# Micro_Clock.net
KiCad netlist of a schematic drawn in Altium Designer
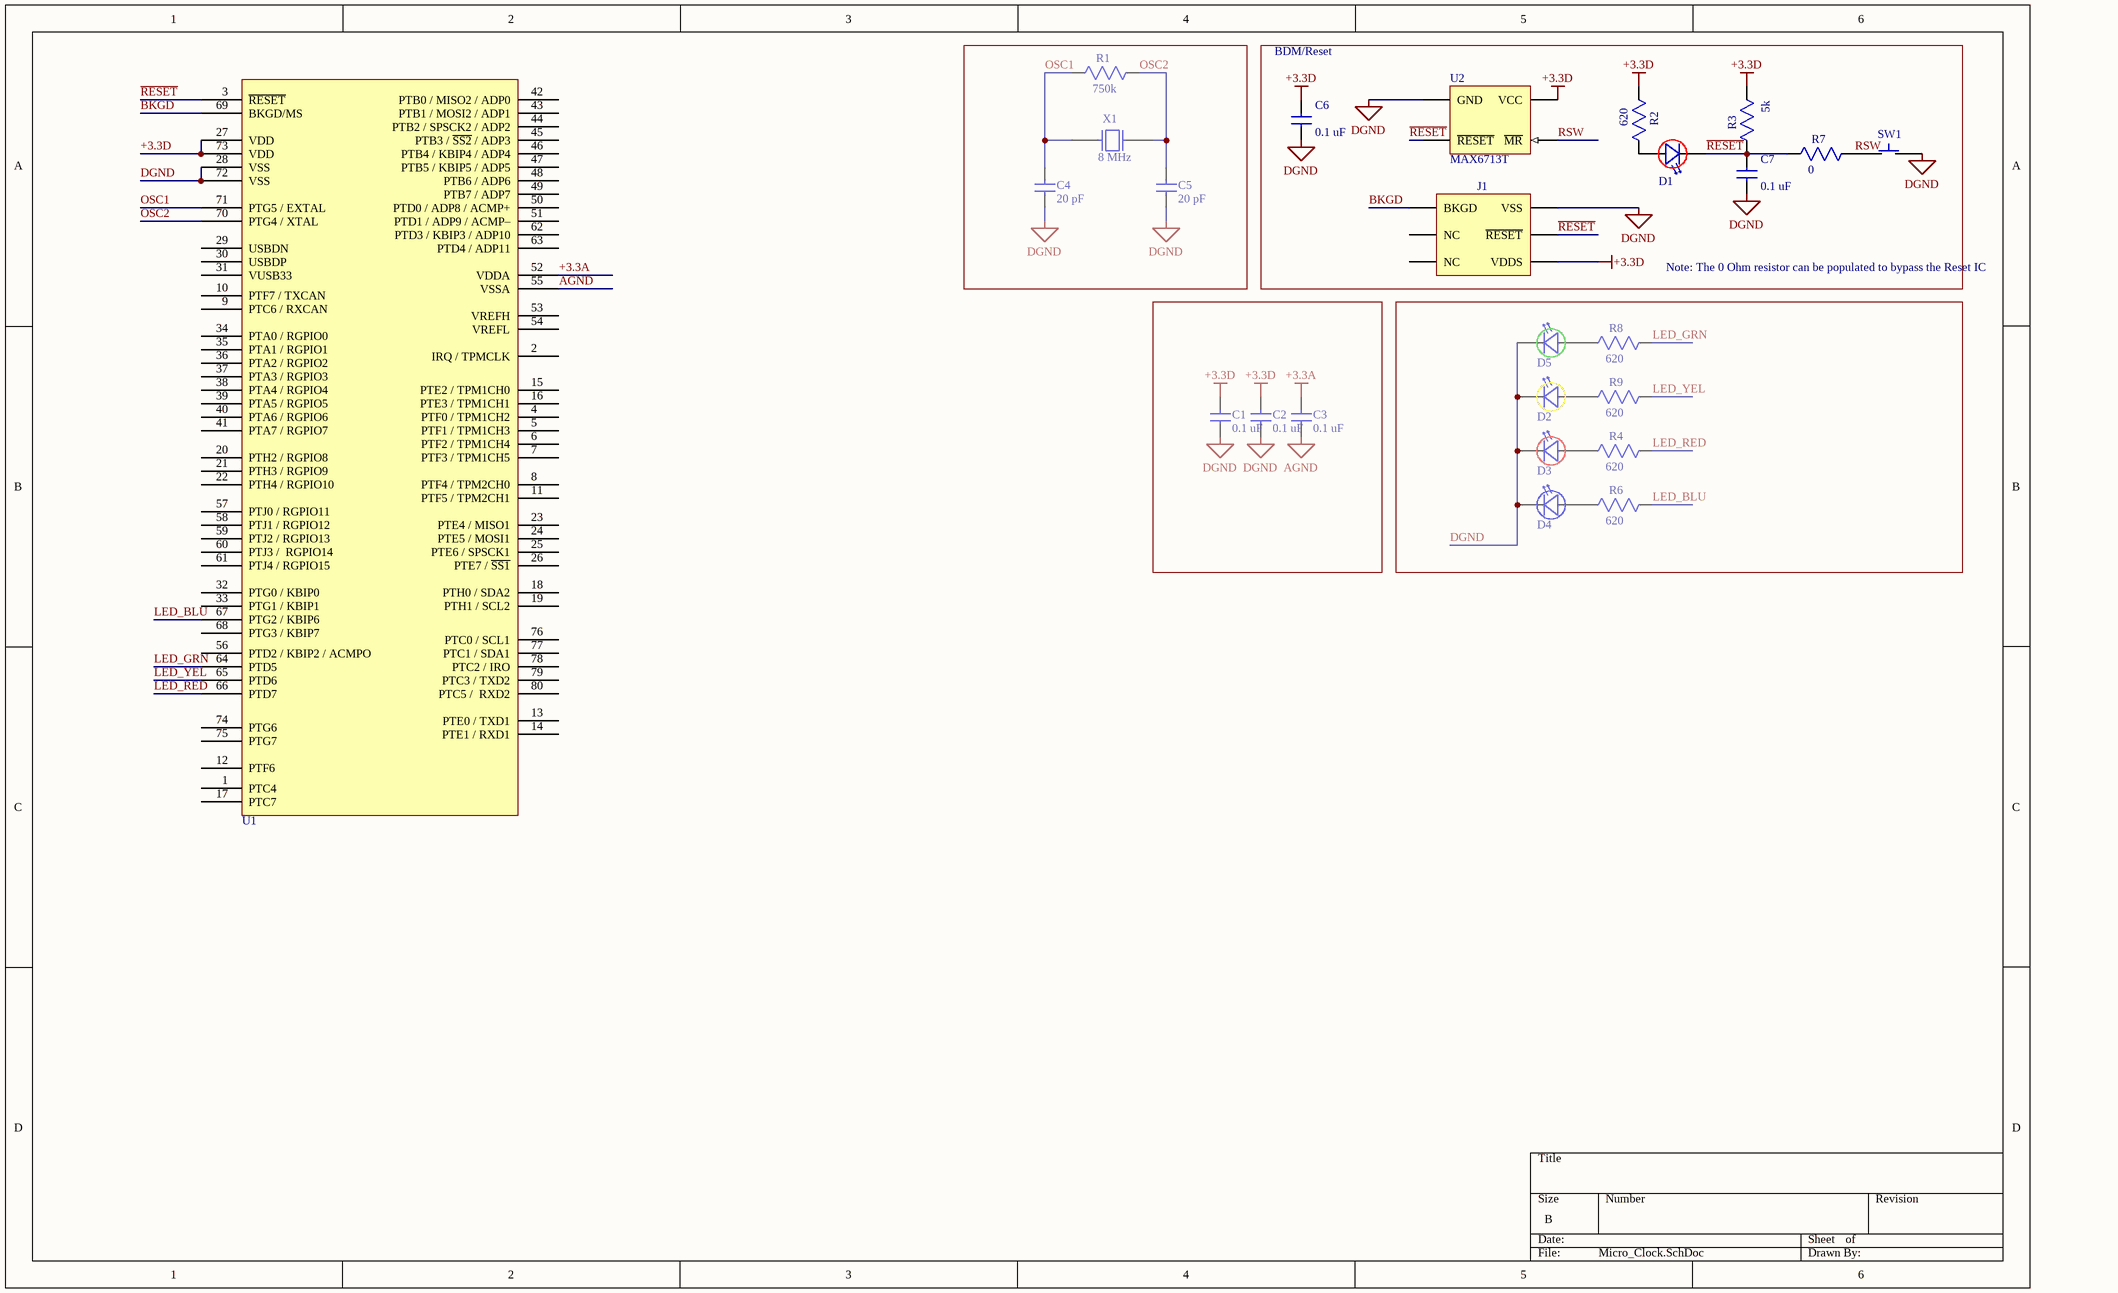
[diagram p0: Micro_Clock.SchDoc]

(export (version "E")
  (design (tool "Eeschema 10.0.6"))
  (components
    (comp (ref "C1")
      (value "0.1 uF")
      (footprint "0805")
      (description "CAP CERM 0.1uF")
      (fields
        (field (name "MANUFACTURER") "Yageo")
        (field (name "Comment") "CAP 0.1uF")
        (field (name "SVP CREATOR") "Brett Paulsen")
      )
      (libsource (lib "c3_SchLib") (part "C_0805_0.1uF_1"))
    )
    (comp (ref "C2")
      (value "0.1 uF")
      (footprint "0805")
      (description "CAP CERM 0.1uF")
      (fields
        (field (name "MANUFACTURER") "Yageo")
        (field (name "Comment") "CAP 0.1uF")
        (field (name "SVP CREATOR") "Brett Paulsen")
      )
      (libsource (lib "c3_SchLib") (part "C_0805_0.1uF_1"))
    )
    (comp (ref "C3")
      (value "0.1 uF")
      (footprint "0805")
      (description "CAP CERM 0.1uF")
      (fields
        (field (name "MANUFACTURER") "Yageo")
        (field (name "Comment") "CAP 0.1uF")
        (field (name "SVP CREATOR") "Brett Paulsen")
      )
      (libsource (lib "c3_SchLib") (part "C_0805_0.1uF_1"))
    )
    (comp (ref "C4")
      (value "20 pF")
      (footprint "0805")
      (description "CAP CERM 20PF 5% 100V NP0 0805")
      (fields
        (field (name "MANUFACTURER") "AVX")
        (field (name "Comment") "CAP 20PF")
        (field (name "SVP CREATOR") "Jonathan Nutzmann")
      )
      (libsource (lib "c3_SchLib") (part "C_0805_20PF_100V_5%"))
    )
    (comp (ref "C5")
      (value "20 pF")
      (footprint "0805")
      (description "CAP CERM 20PF 5% 100V NP0 0805")
      (fields
        (field (name "MANUFACTURER") "AVX")
        (field (name "Comment") "CAP 20PF")
        (field (name "SVP CREATOR") "Jonathan Nutzmann")
      )
      (libsource (lib "c3_SchLib") (part "C_0805_20PF_100V_5%"))
    )
    (comp (ref "C6")
      (value "0.1 uF")
      (footprint "0805")
      (description "CAP CERM 0.1uF")
      (fields
        (field (name "MANUFACTURER") "Yageo")
        (field (name "Comment") "CAP 0.1uF")
        (field (name "SVP CREATOR") "Brett Paulsen")
      )
      (libsource (lib "c3_SchLib") (part "C_0805_0.1uF_1"))
    )
    (comp (ref "C7")
      (value "0.1 uF")
      (footprint "0805")
      (description "CAP CERM 0.1uF")
      (fields
        (field (name "MANUFACTURER") "Yageo")
        (field (name "Comment") "CAP 0.1uF")
        (field (name "SVP CREATOR") "Brett Paulsen")
      )
      (libsource (lib "c3_SchLib") (part "C_0805_0.1uF_1"))
    )
    (comp (ref "D1")
      (value "D_LED_0805_RED")
      (footprint "0805P")
      (description "LED CHIPLED 645NM RED DIFF 0805")
      (fields (field (name "SVP CREATOR") "Jonathan Nutzmann"))
      (libsource (lib "c3_SchLib") (part "D_LED_0805_RED"))
    )
    (comp (ref "D2")
      (value "D_LED_0805_YELLOW")
      (footprint "0805P")
      (description "LED 595NM AMBER DIFF SMD 0805")
      (fields (field (name "SVP CREATOR") "Jonathan Nutzmann"))
      (libsource (lib "c3_SchLib") (part "D_LED_0805_YELLOW"))
    )
    (comp (ref "D3")
      (value "D_LED_0805_RED")
      (footprint "0805P")
      (description "LED CHIPLED 645NM RED DIFF 0805")
      (fields (field (name "SVP CREATOR") "Jonathan Nutzmann"))
      (libsource (lib "c3_SchLib") (part "D_LED_0805_RED"))
    )
    (comp (ref "D4")
      (value "D_LED_0805_BLUE")
      (footprint "0805P")
      (description "LED 2X1.2MM 470NM BL WTR CLR SMD")
      (fields (field (name "SVP CREATOR") "Jonathan Nutzmann"))
      (libsource (lib "c3_SchLib") (part "D_LED_0805_BLUE"))
    )
    (comp (ref "D5")
      (value "D_LED_0805_GREEN")
      (footprint "0805P")
      (description "LED CHIPLED 570NM GREEN 0805 SMD")
      (fields
        (field (name "MANUFACTURER") "Osram Opto Semiconductors Inc")
        (field (name "SVP CREATOR") "Nate Bolyard")
        (field (name "SVP REVIEWER 1") "Trevtron")
      )
      (libsource (lib "c3_SchLib") (part "D_LED_0805_GREEN"))
    )
    (comp (ref "J1")
      (value "BDM HHEADER")
      (footprint "BDM_HEADER")
      (description "BDM HEADER")
      (fields (field (name "SVP CREATOR") "Nate Bolyard"))
      (libsource (lib "c3_SchLib") (part "J_BDM_HEADER"))
    )
    (comp (ref "R1")
      (value "750k")
      (footprint "0805")
      (description "RES 750K OHM 1/8W 1% 0805 SMD")
      (fields
        (field (name "MANUFACTURER") "Rohm Semiconductor")
        (field (name "Comment") "R_0805_750k_1%")
        (field (name "SVP CREATOR") "Jonathan Nutzmann")
      )
      (libsource (lib "c3_SchLib") (part "R_0805_750k_1%"))
    )
    (comp (ref "R2")
      (value "620")
      (footprint "0805")
      (description "RES 620 OHM 1/8W 1% 0805 SMD")
      (fields (field (name "Comment") "R_0805_620_1%") (field (name "SVP CREATOR") "Jonathan Nutzmann"))
      (libsource (lib "c3_SchLib") (part "R_0805_620_1%"))
    )
    (comp (ref "R3")
      (value "5k")
      (footprint "0805")
      (description "RES 5K OHM 1/8W 1% 0805 SMD")
      (fields (field (name "Comment") "R_0805_5k") (field (name "SVP CREATOR") "Jonathan Nutzmann"))
      (libsource (lib "c3_SchLib") (part "R_0805_5K_1%"))
    )
    (comp (ref "R4")
      (value "620")
      (footprint "0805")
      (description "RES 620 OHM 1/8W 1% 0805 SMD")
      (fields (field (name "Comment") "R_0805_620_1%") (field (name "SVP CREATOR") "Jonathan Nutzmann"))
      (libsource (lib "c3_SchLib") (part "R_0805_620_1%"))
    )
    (comp (ref "R6")
      (value "620")
      (footprint "0805")
      (description "RES 620 OHM 1/8W 1% 0805 SMD")
      (fields (field (name "Comment") "R_0805_620_1%") (field (name "SVP CREATOR") "Jonathan Nutzmann"))
      (libsource (lib "c3_SchLib") (part "R_0805_620_1%"))
    )
    (comp (ref "R7")
      (value "0")
      (footprint "0805")
      (description "RES 0 OHM 0805 SMD")
      (fields (field (name "Comment") "R_0805_0") (field (name "SVP CREATOR") "Jonathan Nutzmann"))
      (libsource (lib "c3_SchLib") (part "R_0805_0"))
    )
    (comp (ref "R8")
      (value "620")
      (footprint "0805")
      (description "RES 620 OHM 1/8W 1% 0805 SMD")
      (fields (field (name "Comment") "R_0805_620_1%") (field (name "SVP CREATOR") "Jonathan Nutzmann"))
      (libsource (lib "c3_SchLib") (part "R_0805_620_1%"))
    )
    (comp (ref "R9")
      (value "620")
      (footprint "0805")
      (description "RES 620 OHM 1/8W 1% 0805 SMD")
      (fields (field (name "Comment") "R_0805_620_1%") (field (name "SVP CREATOR") "Jonathan Nutzmann"))
      (libsource (lib "c3_SchLib") (part "R_0805_620_1%"))
    )
    (comp (ref "SW1")
      (value "SW_TACT_SWITCH_6x6")
      (footprint "TACT_SWITCH_6x6")
      (description "SWITCH TACT 6MM BLACK 160GF")
      (fields (field (name "MANUFACTURER") "Tyco Electronics") (field (name "SVP CREATOR") "Nate Bolyard"))
      (libsource (lib "c3_SchLib") (part "SW_TACT_SWITCH_6x6"))
    )
    (comp (ref "U1")
      (value "C3 Microcontroller")
      (footprint "QFN_80_65P")
      (description "IC MCU 128/16K FLASH/SRAM 80LQFP")
      (fields (field (name "MANUFACTURER") "Microchip") (field (name "SVP CREATOR") "Jonathan Nutzmann"))
      (libsource (lib "c3_SchLib") (part "U_MCF51JM128VLK"))
    )
    (comp (ref "U2")
      (value "MAX6713T")
      (footprint "SC70")
      (description "MAX6713T Reset controller")
      (fields
        (field (name "MANUFACTURER") "Maxim")
        (field (name "Comment") "U_MAX6713T")
        (field (name "SVP CREATOR") "Nate Bolyard")
      )
      (libsource (lib "c3_SchLib") (part "U_MAX6713T"))
    )
    (comp (ref "X1")
      (value "8 MHz")
      (footprint "HC-49")
      (description "CRYSTAL 8.00 MHZ 20PF 49US")
      (fields
        (field (name "MANUFACTURER") "ECS")
        (field (name "Comment") "HC49")
        (field (name "SVP CREATOR") "Jonathan Nutzmann")
      )
      (libsource (lib "c3_SchLib") (part "X_HC49"))
    )
  )
  (nets
    (net (code "1") (name "+3.3A") (class "Default")
      (node (ref "C3") (pin "2") (pinfunction "2_2") (pintype "passive"))
      (node (ref "U1") (pin "52") (pinfunction "VDDA_52") (pintype "passive"))
    )
    (net (code "2") (name "+3.3D") (class "Default")
      (node (ref "C1") (pin "2") (pinfunction "2_2") (pintype "passive"))
      (node (ref "C2") (pin "1") (pinfunction "1_1") (pintype "passive"))
      (node (ref "C6") (pin "2") (pinfunction "2_2") (pintype "passive"))
      (node (ref "J1") (pin "4") (pinfunction "VDDS_4") (pintype "passive"))
      (node (ref "R2") (pin "2") (pinfunction "2_2") (pintype "passive"))
      (node (ref "R3") (pin "1") (pinfunction "1_1") (pintype "passive"))
      (node (ref "U1") (pin "27") (pinfunction "VDD_27") (pintype "passive"))
      (node (ref "U1") (pin "73") (pinfunction "VDD_73") (pintype "passive"))
      (node (ref "U2") (pin "4") (pinfunction "VCC_4") (pintype "power_in"))
    )
    (net (code "3") (name "/BKGD") (class "Default")
      (node (ref "J1") (pin "1") (pinfunction "BKGD_1") (pintype "passive"))
      (node (ref "U1") (pin "69") (pinfunction "BKGD/MS_69") (pintype "passive"))
    )
    (net (code "4") (name "/LED_BLU") (class "Default")
      (node (ref "R6") (pin "1") (pinfunction "1_1") (pintype "passive"))
      (node (ref "U1") (pin "67") (pinfunction "PTG2_/_KBIP6_67") (pintype "passive"))
    )
    (net (code "5") (name "/LED_GRN") (class "Default")
      (node (ref "R8") (pin "1") (pinfunction "1_1") (pintype "passive"))
      (node (ref "U1") (pin "64") (pinfunction "PTD5_64") (pintype "passive"))
    )
    (net (code "6") (name "/LED_RED") (class "Default")
      (node (ref "R4") (pin "1") (pinfunction "1_1") (pintype "passive"))
      (node (ref "U1") (pin "66") (pinfunction "PTD7_66") (pintype "passive"))
    )
    (net (code "7") (name "/LED_YEL") (class "Default")
      (node (ref "R9") (pin "1") (pinfunction "1_1") (pintype "passive"))
      (node (ref "U1") (pin "65") (pinfunction "PTD6_65") (pintype "passive"))
    )
    (net (code "8") (name "/OSC1") (class "Default")
      (node (ref "C4") (pin "1") (pinfunction "1_1") (pintype "passive"))
      (node (ref "R1") (pin "2") (pinfunction "2_2") (pintype "passive"))
      (node (ref "U1") (pin "71") (pinfunction "PTG5_/_EXTAL_71") (pintype "passive"))
      (node (ref "X1") (pin "2") (pinfunction "2_2") (pintype "passive"))
    )
    (net (code "9") (name "/OSC2") (class "Default")
      (node (ref "C5") (pin "1") (pinfunction "1_1") (pintype "passive"))
      (node (ref "R1") (pin "1") (pinfunction "1_1") (pintype "passive"))
      (node (ref "U1") (pin "70") (pinfunction "PTG4_/_XTAL_70") (pintype "passive"))
      (node (ref "X1") (pin "1") (pinfunction "1_1") (pintype "passive"))
    )
    (net (code "10") (name "/RSW") (class "Default")
      (node (ref "R7") (pin "1") (pinfunction "1_1") (pintype "passive"))
      (node (ref "SW1") (pin "1") (pinfunction "1_1") (pintype "passive"))
      (node (ref "U2") (pin "3") (pinfunction "~{MR}_3") (pintype "input"))
    )
    (net (code "11") (name "/~{RESET}") (class "Default")
      (node (ref "C7") (pin "2") (pinfunction "2_2") (pintype "passive"))
      (node (ref "D1") (pin "1") (pinfunction "Cathode_1") (pintype "passive"))
      (node (ref "J1") (pin "5") (pinfunction "~{RESET}_5") (pintype "passive"))
      (node (ref "R3") (pin "2") (pinfunction "2_2") (pintype "passive"))
      (node (ref "R7") (pin "2") (pinfunction "2_2") (pintype "passive"))
      (node (ref "U1") (pin "3") (pinfunction "~{RESET}_3") (pintype "passive"))
      (node (ref "U2") (pin "2") (pinfunction "~{RESET}_2") (pintype "open_collector"))
    )
    (net (code "12") (name "AGND") (class "Default")
      (node (ref "C3") (pin "1") (pinfunction "1_1") (pintype "passive"))
      (node (ref "U1") (pin "55") (pinfunction "VSSA_55") (pintype "passive"))
    )
    (net (code "13") (name "DGND") (class "Default")
      (node (ref "C1") (pin "1") (pinfunction "1_1") (pintype "passive"))
      (node (ref "C2") (pin "2") (pinfunction "2_2") (pintype "passive"))
      (node (ref "C4") (pin "2") (pinfunction "2_2") (pintype "passive"))
      (node (ref "C5") (pin "2") (pinfunction "2_2") (pintype "passive"))
      (node (ref "C6") (pin "1") (pinfunction "1_1") (pintype "passive"))
      (node (ref "C7") (pin "1") (pinfunction "1_1") (pintype "passive"))
      (node (ref "D2") (pin "1") (pinfunction "Cathode_1") (pintype "passive"))
      (node (ref "D3") (pin "1") (pinfunction "Cathode_1") (pintype "passive"))
      (node (ref "D4") (pin "1") (pinfunction "Cathode_1") (pintype "passive"))
      (node (ref "D5") (pin "1") (pinfunction "Cathode_1") (pintype "passive"))
      (node (ref "J1") (pin "6") (pinfunction "VSS_6") (pintype "passive"))
      (node (ref "SW1") (pin "2") (pinfunction "2_2") (pintype "passive"))
      (node (ref "U1") (pin "28") (pinfunction "VSS_28") (pintype "passive"))
      (node (ref "U1") (pin "72") (pinfunction "VSS_72") (pintype "passive"))
      (node (ref "U2") (pin "1") (pinfunction "GND_1") (pintype "power_in"))
    )
    (net (code "14") (name "Net-(D1-Anode)") (class "Default")
      (node (ref "D1") (pin "2") (pinfunction "Anode_2") (pintype "passive"))
      (node (ref "R2") (pin "1") (pinfunction "1_1") (pintype "passive"))
    )
    (net (code "15") (name "Net-(D2-Anode)") (class "Default")
      (node (ref "D2") (pin "2") (pinfunction "Anode_2") (pintype "passive"))
      (node (ref "R9") (pin "2") (pinfunction "2_2") (pintype "passive"))
    )
    (net (code "16") (name "Net-(D3-Anode)") (class "Default")
      (node (ref "D3") (pin "2") (pinfunction "Anode_2") (pintype "passive"))
      (node (ref "R4") (pin "2") (pinfunction "2_2") (pintype "passive"))
    )
    (net (code "17") (name "Net-(D4-Anode)") (class "Default")
      (node (ref "D4") (pin "2") (pinfunction "Anode_2") (pintype "passive"))
      (node (ref "R6") (pin "2") (pinfunction "2_2") (pintype "passive"))
    )
    (net (code "18") (name "Net-(D5-Anode)") (class "Default")
      (node (ref "D5") (pin "2") (pinfunction "Anode_2") (pintype "passive"))
      (node (ref "R8") (pin "2") (pinfunction "2_2") (pintype "passive"))
    )
    (net (code "19") (name "unconnected-(J1-NC-Pad2)") (class "Default")
      (node (ref "J1") (pin "2") (pinfunction "NC_2") (pintype "passive"))
    )
    (net (code "20") (name "unconnected-(J1-NC-Pad3)") (class "Default")
      (node (ref "J1") (pin "3") (pinfunction "NC_3") (pintype "passive"))
    )
    (net (code "21") (name "unconnected-(U1-IRQ_{slash}_TPMCLK-Pad2)") (class "Default")
      (node (ref "U1") (pin "2") (pinfunction "IRQ_/_TPMCLK_2") (pintype "passive"))
    )
    (net (code "22") (name "unconnected-(U1-PTA0_{slash}_RGPIO0-Pad34)") (class "Default")
      (node (ref "U1") (pin "34") (pinfunction "PTA0_/_RGPIO0_34") (pintype "passive"))
    )
    (net (code "23") (name "unconnected-(U1-PTA1_{slash}_RGPIO1-Pad35)") (class "Default")
      (node (ref "U1") (pin "35") (pinfunction "PTA1_/_RGPIO1_35") (pintype "passive"))
    )
    (net (code "24") (name "unconnected-(U1-PTA2_{slash}_RGPIO2-Pad36)") (class "Default")
      (node (ref "U1") (pin "36") (pinfunction "PTA2_/_RGPIO2_36") (pintype "passive"))
    )
    (net (code "25") (name "unconnected-(U1-PTA3_{slash}_RGPIO3-Pad37)") (class "Default")
      (node (ref "U1") (pin "37") (pinfunction "PTA3_/_RGPIO3_37") (pintype "passive"))
    )
    (net (code "26") (name "unconnected-(U1-PTA4_{slash}_RGPIO4-Pad38)") (class "Default")
      (node (ref "U1") (pin "38") (pinfunction "PTA4_/_RGPIO4_38") (pintype "passive"))
    )
    (net (code "27") (name "unconnected-(U1-PTA5_{slash}_RGPIO5-Pad39)") (class "Default")
      (node (ref "U1") (pin "39") (pinfunction "PTA5_/_RGPIO5_39") (pintype "passive"))
    )
    (net (code "28") (name "unconnected-(U1-PTA6_{slash}_RGPIO6-Pad40)") (class "Default")
      (node (ref "U1") (pin "40") (pinfunction "PTA6_/_RGPIO6_40") (pintype "passive"))
    )
    (net (code "29") (name "unconnected-(U1-PTA7_{slash}_RGPIO7-Pad41)") (class "Default")
      (node (ref "U1") (pin "41") (pinfunction "PTA7_/_RGPIO7_41") (pintype "passive"))
    )
    (net (code "30") (name "unconnected-(U1-PTB0_{slash}_MISO2_{slash}_ADP0-Pad42)") (class "Default")
      (node (ref "U1") (pin "42") (pinfunction "PTB0_/_MISO2_/_ADP0_42") (pintype "passive"))
    )
    (net (code "31") (name "unconnected-(U1-PTB1_{slash}_MOSI2_{slash}_ADP1-Pad43)") (class "Default")
      (node (ref "U1") (pin "43") (pinfunction "PTB1_/_MOSI2_/_ADP1_43") (pintype "passive"))
    )
    (net (code "32") (name "unconnected-(U1-PTB2_{slash}_SPSCK2_{slash}_ADP2-Pad44)") (class "Default")
      (node (ref "U1") (pin "44") (pinfunction "PTB2_/_SPSCK2_/_ADP2_44") (pintype "passive"))
    )
    (net (code "33") (name "unconnected-(U1-PTB3_{slash}_~{SS2}_{slash}_ADP3-Pad45)") (class "Default")
      (node (ref "U1") (pin "45") (pinfunction "PTB3_/_~{SS2}_/_ADP3_45") (pintype "passive"))
    )
    (net (code "34") (name "unconnected-(U1-PTB4_{slash}_KBIP4_{slash}_ADP4-Pad46)") (class "Default")
      (node (ref "U1") (pin "46") (pinfunction "PTB4_/_KBIP4_/_ADP4_46") (pintype "passive"))
    )
    (net (code "35") (name "unconnected-(U1-PTB5_{slash}_KBIP5_{slash}_ADP5-Pad47)") (class "Default")
      (node (ref "U1") (pin "47") (pinfunction "PTB5_/_KBIP5_/_ADP5_47") (pintype "passive"))
    )
    (net (code "36") (name "unconnected-(U1-PTB6_{slash}_ADP6-Pad48)") (class "Default")
      (node (ref "U1") (pin "48") (pinfunction "PTB6_/_ADP6_48") (pintype "passive"))
    )
    (net (code "37") (name "unconnected-(U1-PTB7_{slash}_ADP7-Pad49)") (class "Default")
      (node (ref "U1") (pin "49") (pinfunction "PTB7_/_ADP7_49") (pintype "passive"))
    )
    (net (code "38") (name "unconnected-(U1-PTC0_{slash}_SCL1-Pad76)") (class "Default")
      (node (ref "U1") (pin "76") (pinfunction "PTC0_/_SCL1_76") (pintype "passive"))
    )
    (net (code "39") (name "unconnected-(U1-PTC1_{slash}_SDA1-Pad77)") (class "Default")
      (node (ref "U1") (pin "77") (pinfunction "PTC1_/_SDA1_77") (pintype "passive"))
    )
    (net (code "40") (name "unconnected-(U1-PTC2_{slash}_IRO-Pad78)") (class "Default")
      (node (ref "U1") (pin "78") (pinfunction "PTC2_/_IRO_78") (pintype "passive"))
    )
    (net (code "41") (name "unconnected-(U1-PTC3_{slash}_TXD2-Pad79)") (class "Default")
      (node (ref "U1") (pin "79") (pinfunction "PTC3_/_TXD2_79") (pintype "passive"))
    )
    (net (code "42") (name "unconnected-(U1-PTC4-Pad1)") (class "Default")
      (node (ref "U1") (pin "1") (pinfunction "PTC4_1") (pintype "passive"))
    )
    (net (code "43") (name "unconnected-(U1-PTC5_{slash}__RXD2-Pad80)") (class "Default")
      (node (ref "U1") (pin "80") (pinfunction "PTC5_/__RXD2_80") (pintype "passive"))
    )
    (net (code "44") (name "unconnected-(U1-PTC6_{slash}_RXCAN-Pad9)") (class "Default")
      (node (ref "U1") (pin "9") (pinfunction "PTC6_/_RXCAN_9") (pintype "passive"))
    )
    (net (code "45") (name "unconnected-(U1-PTC7-Pad17)") (class "Default")
      (node (ref "U1") (pin "17") (pinfunction "PTC7_17") (pintype "passive"))
    )
    (net (code "46") (name "unconnected-(U1-PTD0_{slash}_ADP8_{slash}_ACMP+-Pad50)") (class "Default")
      (node (ref "U1") (pin "50") (pinfunction "PTD0_/_ADP8_/_ACMP+_50") (pintype "passive"))
    )
    (net (code "47") (name "unconnected-(U1-PTD1_{slash}_ADP9_{slash}_ACMP-Pad51)") (class "Default")
      (node (ref "U1") (pin "51") (pinfunction "PTD1_/_ADP9_/_ACMP_51") (pintype "passive"))
    )
    (net (code "48") (name "unconnected-(U1-PTD2_{slash}_KBIP2_{slash}_ACMPO-Pad56)") (class "Default")
      (node (ref "U1") (pin "56") (pinfunction "PTD2_/_KBIP2_/_ACMPO_56") (pintype "passive"))
    )
    (net (code "49") (name "unconnected-(U1-PTD3_{slash}_KBIP3_{slash}_ADP10-Pad62)") (class "Default")
      (node (ref "U1") (pin "62") (pinfunction "PTD3_/_KBIP3_/_ADP10_62") (pintype "passive"))
    )
    (net (code "50") (name "unconnected-(U1-PTD4_{slash}_ADP11-Pad63)") (class "Default")
      (node (ref "U1") (pin "63") (pinfunction "PTD4_/_ADP11_63") (pintype "passive"))
    )
    (net (code "51") (name "unconnected-(U1-PTE0_{slash}_TXD1-Pad13)") (class "Default")
      (node (ref "U1") (pin "13") (pinfunction "PTE0_/_TXD1_13") (pintype "passive"))
    )
    (net (code "52") (name "unconnected-(U1-PTE1_{slash}_RXD1-Pad14)") (class "Default")
      (node (ref "U1") (pin "14") (pinfunction "PTE1_/_RXD1_14") (pintype "passive"))
    )
    (net (code "53") (name "unconnected-(U1-PTE2_{slash}_TPM1CH0-Pad15)") (class "Default")
      (node (ref "U1") (pin "15") (pinfunction "PTE2_/_TPM1CH0_15") (pintype "passive"))
    )
    (net (code "54") (name "unconnected-(U1-PTE3_{slash}_TPM1CH1-Pad16)") (class "Default")
      (node (ref "U1") (pin "16") (pinfunction "PTE3_/_TPM1CH1_16") (pintype "passive"))
    )
    (net (code "55") (name "unconnected-(U1-PTE4_{slash}_MISO1-Pad23)") (class "Default")
      (node (ref "U1") (pin "23") (pinfunction "PTE4_/_MISO1_23") (pintype "passive"))
    )
    (net (code "56") (name "unconnected-(U1-PTE5_{slash}_MOSI1-Pad24)") (class "Default")
      (node (ref "U1") (pin "24") (pinfunction "PTE5_/_MOSI1_24") (pintype "passive"))
    )
    (net (code "57") (name "unconnected-(U1-PTE6_{slash}_SPSCK1-Pad25)") (class "Default")
      (node (ref "U1") (pin "25") (pinfunction "PTE6_/_SPSCK1_25") (pintype "passive"))
    )
    (net (code "58") (name "unconnected-(U1-PTE7_{slash}_~{SS1}-Pad26)") (class "Default")
      (node (ref "U1") (pin "26") (pinfunction "PTE7_/_~{SS1}_26") (pintype "passive"))
    )
    (net (code "59") (name "unconnected-(U1-PTF0_{slash}_TPM1CH2-Pad4)") (class "Default")
      (node (ref "U1") (pin "4") (pinfunction "PTF0_/_TPM1CH2_4") (pintype "passive"))
    )
    (net (code "60") (name "unconnected-(U1-PTF1_{slash}_TPM1CH3-Pad5)") (class "Default")
      (node (ref "U1") (pin "5") (pinfunction "PTF1_/_TPM1CH3_5") (pintype "passive"))
    )
    (net (code "61") (name "unconnected-(U1-PTF2_{slash}_TPM1CH4-Pad6)") (class "Default")
      (node (ref "U1") (pin "6") (pinfunction "PTF2_/_TPM1CH4_6") (pintype "passive"))
    )
    (net (code "62") (name "unconnected-(U1-PTF3_{slash}_TPM1CH5-Pad7)") (class "Default")
      (node (ref "U1") (pin "7") (pinfunction "PTF3_/_TPM1CH5_7") (pintype "passive"))
    )
    (net (code "63") (name "unconnected-(U1-PTF4_{slash}_TPM2CH0-Pad8)") (class "Default")
      (node (ref "U1") (pin "8") (pinfunction "PTF4_/_TPM2CH0_8") (pintype "passive"))
    )
    (net (code "64") (name "unconnected-(U1-PTF5_{slash}_TPM2CH1-Pad11)") (class "Default")
      (node (ref "U1") (pin "11") (pinfunction "PTF5_/_TPM2CH1_11") (pintype "passive"))
    )
    (net (code "65") (name "unconnected-(U1-PTF6-Pad12)") (class "Default")
      (node (ref "U1") (pin "12") (pinfunction "PTF6_12") (pintype "passive"))
    )
    (net (code "66") (name "unconnected-(U1-PTF7_{slash}_TXCAN-Pad10)") (class "Default")
      (node (ref "U1") (pin "10") (pinfunction "PTF7_/_TXCAN_10") (pintype "passive"))
    )
    (net (code "67") (name "unconnected-(U1-PTG0_{slash}_KBIP0-Pad32)") (class "Default")
      (node (ref "U1") (pin "32") (pinfunction "PTG0_/_KBIP0_32") (pintype "passive"))
    )
    (net (code "68") (name "unconnected-(U1-PTG1_{slash}_KBIP1-Pad33)") (class "Default")
      (node (ref "U1") (pin "33") (pinfunction "PTG1_/_KBIP1_33") (pintype "passive"))
    )
    (net (code "69") (name "unconnected-(U1-PTG3_{slash}_KBIP7-Pad68)") (class "Default")
      (node (ref "U1") (pin "68") (pinfunction "PTG3_/_KBIP7_68") (pintype "passive"))
    )
    (net (code "70") (name "unconnected-(U1-PTG6-Pad74)") (class "Default")
      (node (ref "U1") (pin "74") (pinfunction "PTG6_74") (pintype "passive"))
    )
    (net (code "71") (name "unconnected-(U1-PTG7-Pad75)") (class "Default")
      (node (ref "U1") (pin "75") (pinfunction "PTG7_75") (pintype "passive"))
    )
    (net (code "72") (name "unconnected-(U1-PTH0_{slash}_SDA2-Pad18)") (class "Default")
      (node (ref "U1") (pin "18") (pinfunction "PTH0_/_SDA2_18") (pintype "passive"))
    )
    (net (code "73") (name "unconnected-(U1-PTH1_{slash}_SCL2-Pad19)") (class "Default")
      (node (ref "U1") (pin "19") (pinfunction "PTH1_/_SCL2_19") (pintype "passive"))
    )
    (net (code "74") (name "unconnected-(U1-PTH2_{slash}_RGPIO8-Pad20)") (class "Default")
      (node (ref "U1") (pin "20") (pinfunction "PTH2_/_RGPIO8_20") (pintype "passive"))
    )
    (net (code "75") (name "unconnected-(U1-PTH3_{slash}_RGPIO9-Pad21)") (class "Default")
      (node (ref "U1") (pin "21") (pinfunction "PTH3_/_RGPIO9_21") (pintype "passive"))
    )
    (net (code "76") (name "unconnected-(U1-PTH4_{slash}_RGPIO10-Pad22)") (class "Default")
      (node (ref "U1") (pin "22") (pinfunction "PTH4_/_RGPIO10_22") (pintype "passive"))
    )
    (net (code "77") (name "unconnected-(U1-PTJ0_{slash}_RGPIO11-Pad57)") (class "Default")
      (node (ref "U1") (pin "57") (pinfunction "PTJ0_/_RGPIO11_57") (pintype "passive"))
    )
    (net (code "78") (name "unconnected-(U1-PTJ1_{slash}_RGPIO12-Pad58)") (class "Default")
      (node (ref "U1") (pin "58") (pinfunction "PTJ1_/_RGPIO12_58") (pintype "passive"))
    )
    (net (code "79") (name "unconnected-(U1-PTJ2_{slash}_RGPIO13-Pad59)") (class "Default")
      (node (ref "U1") (pin "59") (pinfunction "PTJ2_/_RGPIO13_59") (pintype "passive"))
    )
    (net (code "80") (name "unconnected-(U1-PTJ3_{slash}__RGPIO14-Pad60)") (class "Default")
      (node (ref "U1") (pin "60") (pinfunction "PTJ3_/__RGPIO14_60") (pintype "passive"))
    )
    (net (code "81") (name "unconnected-(U1-PTJ4_{slash}_RGPIO15-Pad61)") (class "Default")
      (node (ref "U1") (pin "61") (pinfunction "PTJ4_/_RGPIO15_61") (pintype "passive"))
    )
    (net (code "82") (name "unconnected-(U1-USBDN-Pad29)") (class "Default")
      (node (ref "U1") (pin "29") (pinfunction "USBDN_29") (pintype "passive"))
    )
    (net (code "83") (name "unconnected-(U1-USBDP-Pad30)") (class "Default")
      (node (ref "U1") (pin "30") (pinfunction "USBDP_30") (pintype "passive"))
    )
    (net (code "84") (name "unconnected-(U1-VREFH-Pad53)") (class "Default")
      (node (ref "U1") (pin "53") (pinfunction "VREFH_53") (pintype "passive"))
    )
    (net (code "85") (name "unconnected-(U1-VREFL-Pad54)") (class "Default")
      (node (ref "U1") (pin "54") (pinfunction "VREFL_54") (pintype "passive"))
    )
    (net (code "86") (name "unconnected-(U1-VUSB33-Pad31)") (class "Default")
      (node (ref "U1") (pin "31") (pinfunction "VUSB33_31") (pintype "passive"))
    )
  )
)
